# espertowatch_v2.net
KiCad netlist of a schematic drawn in EAGLE
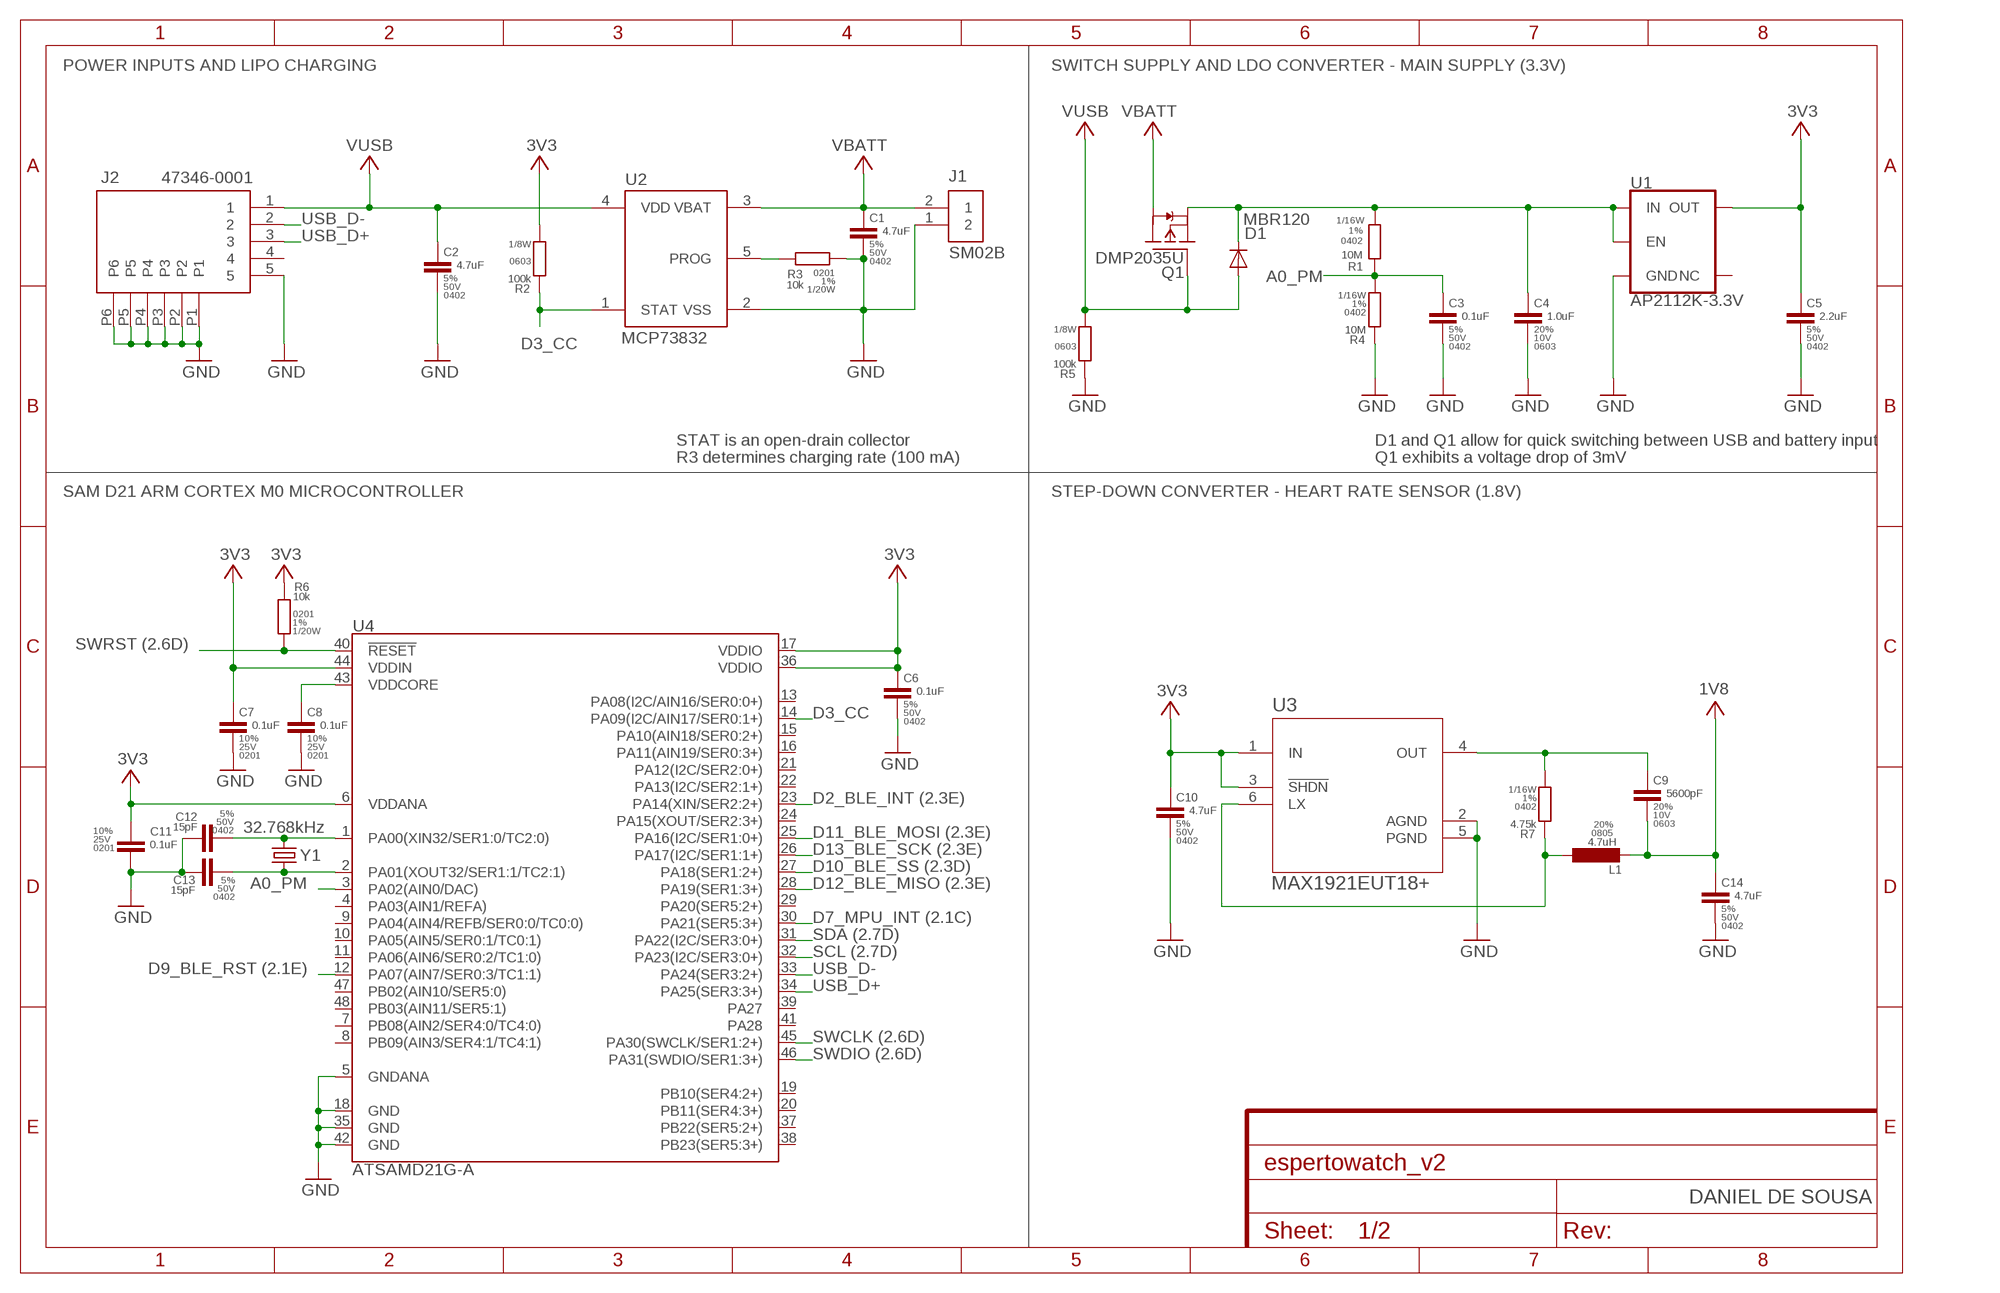
[diagram p0: schematic, sheet 1]
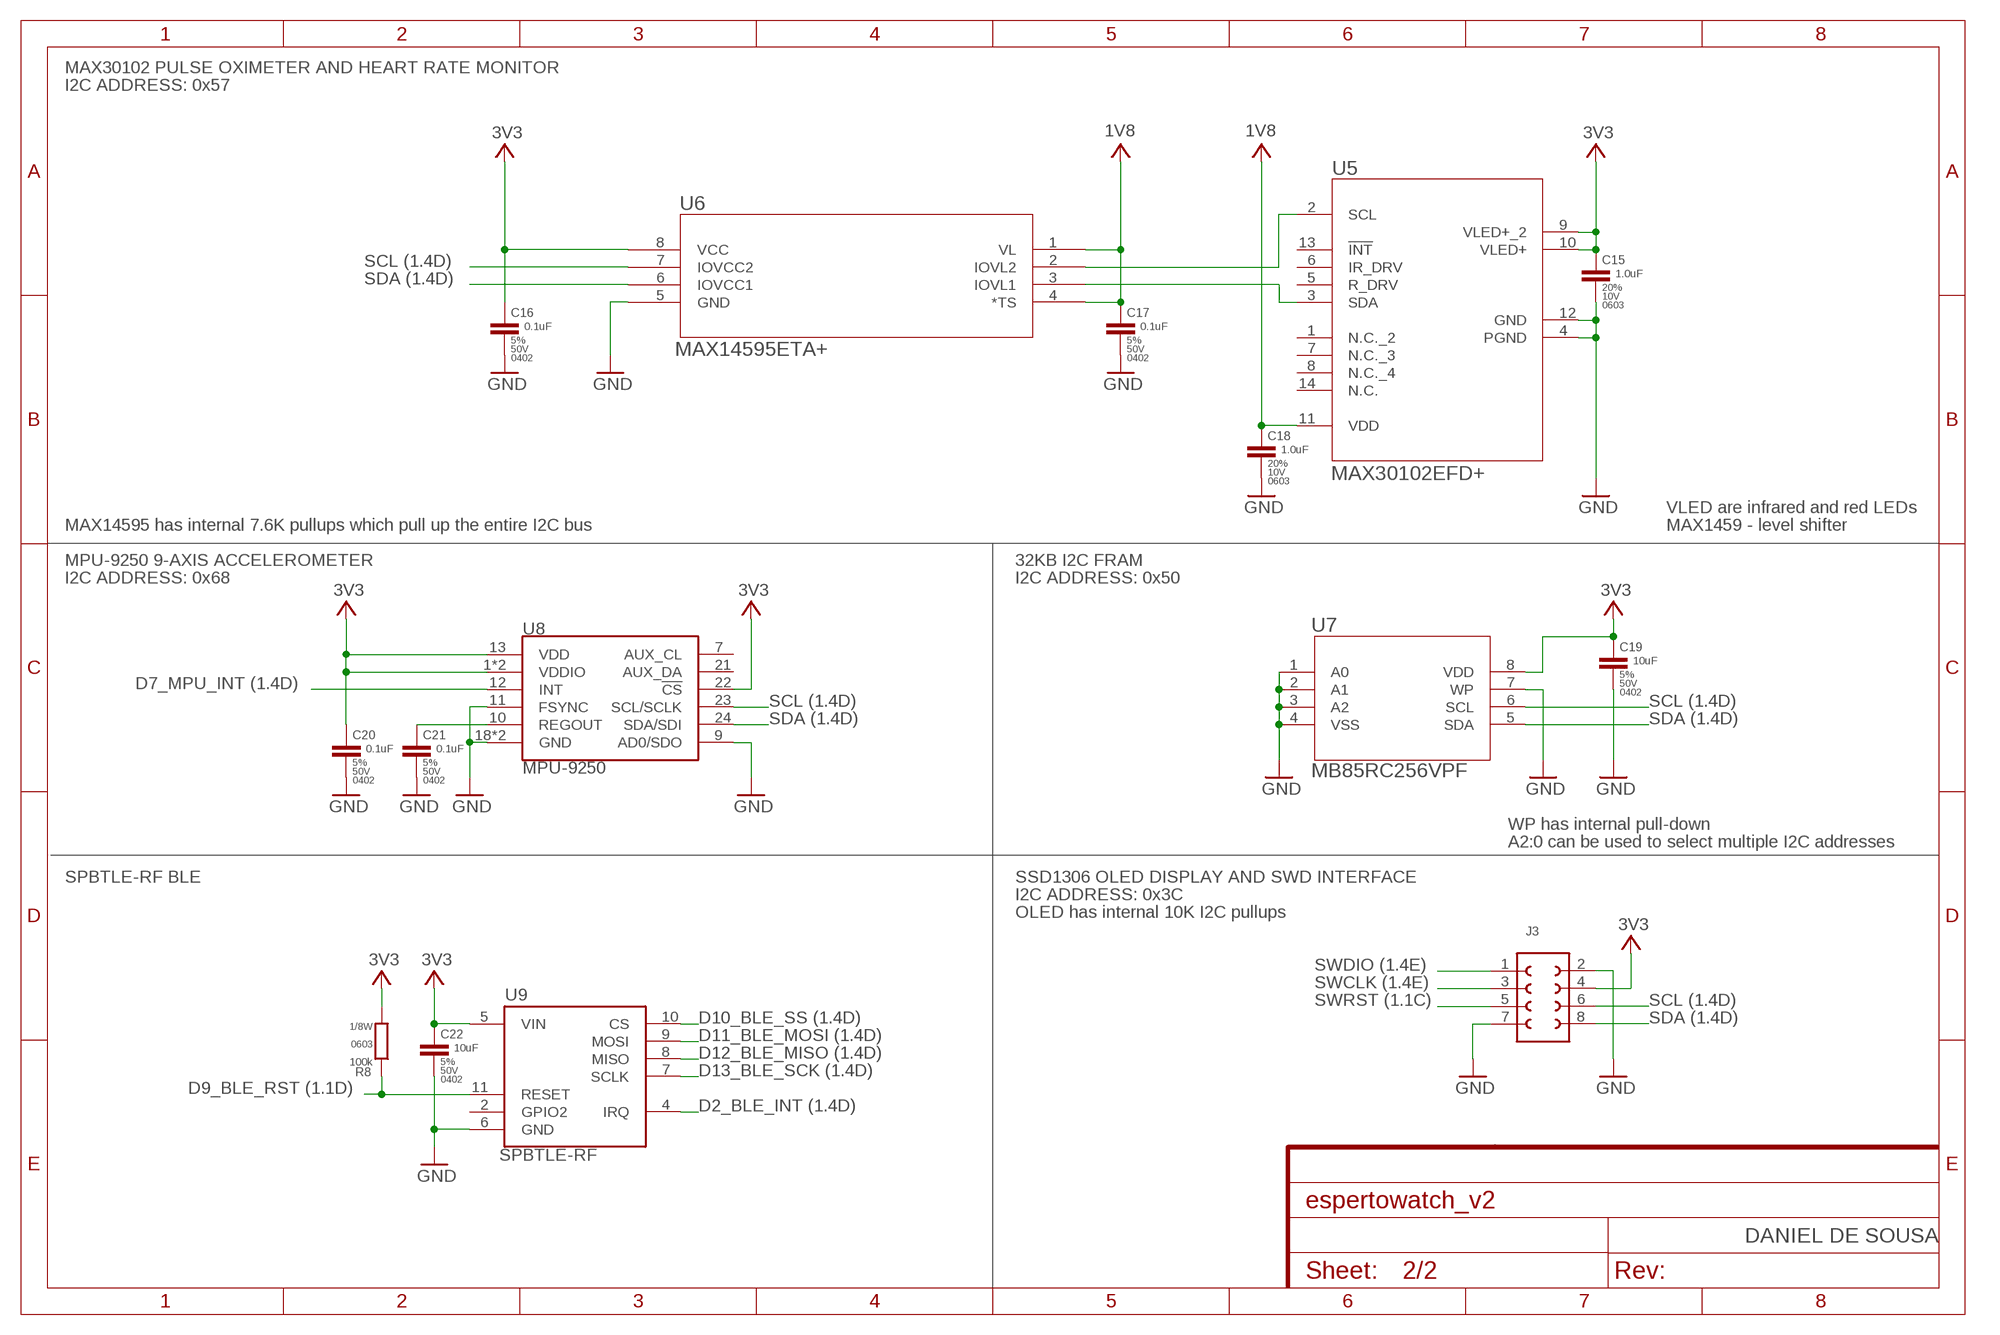
[diagram p1: schematic, sheet 2]

(export (version "E")
  (design (tool "Eeschema 10.0.6"))
  (components
    (comp (ref "C1")
      (value "4.7uF")
      (footprint "eagle-import:C0402_MURATA_GRM15-GJM15")
      (fields (field (name "TOLERANCE") "5%"))
      (libsource (lib "eagle-import") (part "C-EUC0402_MURATA_GRM15-GJM15"))
    )
    (comp (ref "C2")
      (value "4.7uF")
      (footprint "eagle-import:C0402_MURATA_GRM15-GJM15")
      (fields (field (name "TOLERANCE") "5%"))
      (libsource (lib "eagle-import") (part "C-EUC0402_MURATA_GRM15-GJM15"))
    )
    (comp (ref "C3")
      (value "0.1uF")
      (footprint "eagle-import:C0402_MURATA_GRM15-GJM15")
      (fields (field (name "TOLERANCE") "5%"))
      (libsource (lib "eagle-import") (part "C-EUC0402_MURATA_GRM15-GJM15"))
    )
    (comp (ref "C4")
      (value "1.0uF")
      (footprint "eagle-import:C0603_MURATA_GRM18")
      (fields (field (name "TOLERANCE") "20%"))
      (libsource (lib "eagle-import") (part "C-EUC0603_MURATA_GRM18"))
    )
    (comp (ref "C5")
      (value "2.2uF")
      (footprint "eagle-import:C0402_MURATA_GRM15-GJM15")
      (fields (field (name "TOLERANCE") "5%"))
      (libsource (lib "eagle-import") (part "C-EUC0402_MURATA_GRM15-GJM15"))
    )
    (comp (ref "C6")
      (value "0.1uF")
      (footprint "eagle-import:C0402_MURATA_GRM15-GJM15")
      (fields (field (name "TOLERANCE") "5%"))
      (libsource (lib "eagle-import") (part "C-EUC0402_MURATA_GRM15-GJM15"))
    )
    (comp (ref "C7")
      (value "0.1uF")
      (footprint "eagle-import:C0201_MURATA_GRM03")
      (fields (field (name "TOLERANCE") "10%"))
      (libsource (lib "eagle-import") (part "C-EUC0201_MURATA_GRM03"))
    )
    (comp (ref "C8")
      (value "0.1uF")
      (footprint "eagle-import:C0201_MURATA_GRM03")
      (fields (field (name "TOLERANCE") "10%"))
      (libsource (lib "eagle-import") (part "C-EUC0201_MURATA_GRM03"))
    )
    (comp (ref "C9")
      (value "5600pF")
      (footprint "eagle-import:C0603_MURATA_GRM18")
      (fields (field (name "TOLERANCE") "20%"))
      (libsource (lib "eagle-import") (part "C-EUC0603_MURATA_GRM18"))
    )
    (comp (ref "C10")
      (value "4.7uF")
      (footprint "eagle-import:C0402_MURATA_GRM15-GJM15")
      (fields (field (name "TOLERANCE") "5%"))
      (libsource (lib "eagle-import") (part "C-EUC0402_MURATA_GRM15-GJM15"))
    )
    (comp (ref "C11")
      (value "0.1uF")
      (footprint "eagle-import:C0201_MURATA_GRM03")
      (fields (field (name "RATING") "25V") (field (name "TOLERANCE") "10%") (field (name "PACKAGE") "0201"))
      (libsource (lib "eagle-import") (part "C-EUC0201_MURATA_GRM03"))
    )
    (comp (ref "C12")
      (value "15pF")
      (footprint "eagle-import:C0402_MURATA_GRM15-GJM15")
      (fields (field (name "RATING") "50V") (field (name "TOLERANCE") "5%") (field (name "PACKAGE") "0402"))
      (libsource (lib "eagle-import") (part "C-EUC0402_MURATA_GRM15-GJM15"))
    )
    (comp (ref "C13")
      (value "15pF")
      (footprint "eagle-import:C0402_MURATA_GRM15-GJM15")
      (fields (field (name "RATING") "50V") (field (name "TOLERANCE") "5%") (field (name "PACKAGE") "0402"))
      (libsource (lib "eagle-import") (part "C-EUC0402_MURATA_GRM15-GJM15"))
    )
    (comp (ref "C14")
      (value "4.7uF")
      (footprint "eagle-import:C0402_MURATA_GRM15-GJM15")
      (fields (field (name "TOLERANCE") "5%"))
      (libsource (lib "eagle-import") (part "C-EUC0402_MURATA_GRM15-GJM15"))
    )
    (comp (ref "D1")
      (value "MBR120")
      (footprint "eagle-import:SOD-123FL")
      (fields (field (name "PARTNO") "AS-ITM-00111"))
      (libsource (lib "eagle-import") (part "AS-ITM-00111"))
    )
    (comp (ref "J1")
      (value "SM02B")
      (footprint "eagle-import:JST_SH_2X1")
      (fields (field (name "PARTNO") "AS-ITM-00231"))
      (libsource (lib "eagle-import") (part "AS-ITM-00231"))
    )
    (comp (ref "J2")
      (value "47346-0001")
      (footprint "eagle-import:MICRO_USB")
      (fields (field (name "PARTNO") "AS-ITM-00021"))
      (libsource (lib "eagle-import") (part "AS-ITM-00021"))
    )
    (comp (ref "L1")
      (value "4.7uH")
      (footprint "eagle-import:L0805_TDK_MLZ")
      (fields (field (name "TOLERANCE") "20%"))
      (libsource (lib "eagle-import") (part "L-EUL0805_TDK_MLZ"))
    )
    (comp (ref "Q1")
      (value "DMP2035U")
      (footprint "eagle-import:SOT23")
      (fields (field (name "PARTNO") "AS-ITM-00024"))
      (libsource (lib "eagle-import") (part "AS-ITM-00024"))
    )
    (comp (ref "R1")
      (value "10M")
      (footprint "eagle-import:R0402_VISHAY_CRCW0402")
      (fields (field (name "TOLERANCE") "1%") (field (name "RATING") "1/16W") (field (name "PACKAGE") "0402"))
      (libsource (lib "eagle-import") (part "CRCW04021M00FKED"))
    )
    (comp (ref "R2")
      (value "100k")
      (footprint "eagle-import:R0603_VISHAY_MCT0603")
      (libsource (lib "eagle-import") (part "R-EU_R0603_VISHAY_MCT0603"))
    )
    (comp (ref "R3")
      (value "10k")
      (footprint "eagle-import:R0201_VISHAY_CRCW0201")
      (fields (field (name "TOLERANCE") "1%") (field (name "RATING") "1/20W") (field (name "PACKAGE") "0201"))
      (libsource (lib "eagle-import") (part "CRCW020110K0FKED"))
    )
    (comp (ref "R4")
      (value "10M")
      (footprint "eagle-import:R0402_VISHAY_CRCW0402")
      (fields (field (name "TOLERANCE") "1%"))
      (libsource (lib "eagle-import") (part "CRCW04021M00FKED"))
    )
    (comp (ref "R5")
      (value "100k")
      (footprint "eagle-import:R0603_VISHAY_MCT0603")
      (libsource (lib "eagle-import") (part "R-EU_R0603_VISHAY_MCT0603"))
    )
    (comp (ref "R6")
      (value "10k")
      (footprint "eagle-import:R0201_VISHAY_CRCW0201")
      (fields (field (name "TOLERANCE") "1%"))
      (libsource (lib "eagle-import") (part "CRCW020110K0FKED"))
    )
    (comp (ref "R7")
      (value "4.75k")
      (footprint "eagle-import:R0402_VISHAY_CRCW0402")
      (fields (field (name "TOLERANCE") "1%"))
      (libsource (lib "eagle-import") (part "R-EU_R0402_VISHAY_CRCW0402"))
    )
    (comp (ref "U1")
      (value "AP2112K-3.3V")
      (footprint "eagle-import:SOT23-5")
      (libsource (lib "eagle-import") (part "V_REG_AP2112K-3.3V"))
    )
    (comp (ref "U2")
      (value "MCP73832")
      (footprint "eagle-import:SOT-23")
      (fields (field (name "PARTNO") "AS-ITM-00136"))
      (libsource (lib "eagle-import") (part "AS-ITM-00136"))
    )
    (comp (ref "U3")
      (value "MAX1921EUT18+")
      (footprint "eagle-import:21-0058I")
      (fields (field (name "MANUFACTURER_PART_NUMBER") "MAX1921EUT18+T"))
      (libsource (lib "eagle-import") (part "MAX1921EUT18+T"))
    )
    (comp (ref "U4")
      (value "ATSAMD21G-A")
      (footprint "eagle-import:TQFP-48")
      (libsource (lib "eagle-import") (part "ATSAMD21G-A"))
    )
    (comp (ref "Y1")
      (value "32.768kHz")
      (footprint "eagle-import:CRYSTAL-SMD-3.2X1.5MM")
      (libsource (lib "eagle-import") (part "CRYSTAL-32.768KHZSMD-3.2X1.5"))
    )
    (comp (ref "C15")
      (value "1.0uF")
      (footprint "eagle-import:C0603_MURATA_GRM18")
      (fields (field (name "TOLERANCE") "20%"))
      (libsource (lib "eagle-import") (part "C-EUC0603_MURATA_GRM18"))
    )
    (comp (ref "C16")
      (value "0.1uF")
      (footprint "eagle-import:C0402_MURATA_GRM15-GJM15")
      (fields (field (name "TOLERANCE") "5%"))
      (libsource (lib "eagle-import") (part "C-EUC0402_MURATA_GRM15-GJM15"))
    )
    (comp (ref "C17")
      (value "0.1uF")
      (footprint "eagle-import:C0402_MURATA_GRM15-GJM15")
      (fields (field (name "TOLERANCE") "5%"))
      (libsource (lib "eagle-import") (part "C-EUC0402_MURATA_GRM15-GJM15"))
    )
    (comp (ref "C18")
      (value "1.0uF")
      (footprint "eagle-import:C0603_MURATA_GRM18")
      (fields (field (name "TOLERANCE") "20%"))
      (libsource (lib "eagle-import") (part "C-EUC0603_MURATA_GRM18"))
    )
    (comp (ref "C19")
      (value "10uF")
      (footprint "eagle-import:C0402_MURATA_GRM15-GJM15")
      (fields (field (name "TOLERANCE") "5%"))
      (libsource (lib "eagle-import") (part "C-EUC0402_MURATA_GRM15-GJM15"))
    )
    (comp (ref "C20")
      (value "0.1uF")
      (footprint "eagle-import:C0402_MURATA_GRM15-GJM15")
      (fields (field (name "TOLERANCE") "5%"))
      (libsource (lib "eagle-import") (part "C-EUC0402_MURATA_GRM15-GJM15"))
    )
    (comp (ref "C21")
      (value "0.1uF")
      (footprint "eagle-import:C0402_MURATA_GRM15-GJM15")
      (fields (field (name "TOLERANCE") "5%"))
      (libsource (lib "eagle-import") (part "C-EUC0402_MURATA_GRM15-GJM15"))
    )
    (comp (ref "C22")
      (value "10uF")
      (footprint "eagle-import:C0402_MURATA_GRM15-GJM15")
      (fields (field (name "TOLERANCE") "5%"))
      (libsource (lib "eagle-import") (part "C-EUC0402_MURATA_GRM15-GJM15"))
    )
    (comp (ref "J3")
      (value "610X08243021")
      (footprint "eagle-import:610X08243021")
      (libsource (lib "eagle-import") (part "610X08243021"))
    )
    (comp (ref "R8")
      (value "100k")
      (footprint "eagle-import:R0603_VISHAY_MCT0603")
      (libsource (lib "eagle-import") (part "R-EU_R0603_VISHAY_MCT0603"))
    )
    (comp (ref "U5")
      (value "MAX30102EFD+")
      (footprint "eagle-import:21-0880B-M")
      (libsource (lib "eagle-import") (part "MAX30102EFD+21-0880B-M"))
    )
    (comp (ref "U6")
      (value "MAX14595ETA+")
      (footprint "eagle-import:21-0487A")
      (fields
        (field (name "DIGI-KEY_PART_NUMBER") "MAX14595ETA+TCT-ND")
        (field (name "MF") "Maxim Integrated")
        (field (name "MP") "MAX14595ETA+T")
      )
      (libsource (lib "eagle-import") (part "MAX14595ETAT"))
    )
    (comp (ref "U7")
      (value "MB85RC256VPF")
      (footprint "eagle-import:FPT-8P-M02")
      (fields (field (name "MANUFACTURER_PART_NUMBER") "Inc."))
      (libsource (lib "eagle-import") (part "INC."))
    )
    (comp (ref "U8")
      (value "MPU-9250")
      (footprint "eagle-import:QFN24-3X3")
      (libsource (lib "eagle-import") (part "MPU-9250"))
    )
    (comp (ref "U9")
      (value "SPBTLE-RF")
      (footprint "eagle-import:SPBTLE-RF")
      (fields (field (name "PARTNO") "AS-ITM-00294"))
      (libsource (lib "eagle-import") (part "AS-ITM-00294"))
    )
  )
  (nets
    (net (code "1") (name "1V8") (class "Default")
      (node (ref "C14") (pin "1") (pinfunction "1_1") (pintype "passive"))
      (node (ref "C17") (pin "1") (pinfunction "1_1") (pintype "passive"))
      (node (ref "C18") (pin "1") (pinfunction "1_1") (pintype "passive"))
      (node (ref "C9") (pin "2") (pinfunction "2_2") (pintype "passive"))
      (node (ref "L1") (pin "P$2") (pinfunction "2_P$2") (pintype "passive"))
      (node (ref "U5") (pin "11") (pinfunction "VDD_11") (pintype "power_in"))
      (node (ref "U6") (pin "1") (pinfunction "VL_1") (pintype "power_in"))
      (node (ref "U6") (pin "4") (pinfunction "*TS_4") (pintype "passive"))
    )
    (net (code "2") (name "3V3") (class "Default")
      (node (ref "C10") (pin "1") (pinfunction "1_1") (pintype "passive"))
      (node (ref "C11") (pin "1") (pinfunction "1_1") (pintype "passive"))
      (node (ref "C15") (pin "1") (pinfunction "1_1") (pintype "passive"))
      (node (ref "C16") (pin "1") (pinfunction "1_1") (pintype "passive"))
      (node (ref "C19") (pin "1") (pinfunction "1_1") (pintype "passive"))
      (node (ref "C20") (pin "1") (pinfunction "1_1") (pintype "passive"))
      (node (ref "C22") (pin "1") (pinfunction "1_1") (pintype "passive"))
      (node (ref "C5") (pin "1") (pinfunction "1_1") (pintype "passive"))
      (node (ref "C6") (pin "1") (pinfunction "1_1") (pintype "passive"))
      (node (ref "C7") (pin "1") (pinfunction "1_1") (pintype "passive"))
      (node (ref "J3") (pin "4") (pinfunction "7_4") (pintype "passive"))
      (node (ref "R2") (pin "2") (pinfunction "2_2") (pintype "passive"))
      (node (ref "R6") (pin "1") (pinfunction "1_1") (pintype "passive"))
      (node (ref "R8") (pin "2") (pinfunction "2_2") (pintype "passive"))
      (node (ref "U1") (pin "5") (pinfunction "OUT_5") (pintype "passive"))
      (node (ref "U3") (pin "1") (pinfunction "IN_1") (pintype "input"))
      (node (ref "U3") (pin "3") (pinfunction "~{SHDN}_3") (pintype "passive"))
      (node (ref "U4") (pin "17") (pinfunction "VDDIO_17") (pintype "bidirectional"))
      (node (ref "U4") (pin "36") (pinfunction "VDDIO_36") (pintype "bidirectional"))
      (node (ref "U4") (pin "44") (pinfunction "VDDIN_44") (pintype "bidirectional"))
      (node (ref "U4") (pin "6") (pinfunction "VDDANA_6") (pintype "bidirectional"))
      (node (ref "U5") (pin "10") (pinfunction "VLED+_10") (pintype "passive"))
      (node (ref "U5") (pin "9") (pinfunction "VLED+_2_9") (pintype "passive"))
      (node (ref "U6") (pin "8") (pinfunction "VCC_8") (pintype "power_in"))
      (node (ref "U7") (pin "8") (pinfunction "VDD_8") (pintype "power_in"))
      (node (ref "U8") (pin "1") (pinfunction "VDDIO_1") (pintype "bidirectional"))
      (node (ref "U8") (pin "13") (pinfunction "VDD_13") (pintype "bidirectional"))
      (node (ref "U8") (pin "22") (pinfunction "~{CS}_22") (pintype "bidirectional"))
      (node (ref "U8") (pin "8") (pinfunction "VDDIO_8") (pintype "bidirectional"))
      (node (ref "U9") (pin "5") (pinfunction "VIN_5") (pintype "bidirectional"))
    )
    (net (code "3") (name "A0_PM") (class "Default")
      (node (ref "C3") (pin "1") (pinfunction "1_1") (pintype "passive"))
      (node (ref "R1") (pin "1") (pinfunction "1_1") (pintype "passive"))
      (node (ref "R4") (pin "2") (pinfunction "2_2") (pintype "passive"))
      (node (ref "U4") (pin "3") (pinfunction "PA02(AIN0/DAC)_3") (pintype "bidirectional"))
    )
    (net (code "4") (name "D2_BLE_INT") (class "Default")
      (node (ref "U4") (pin "23") (pinfunction "PA14(XIN/SER2:2+)_23") (pintype "bidirectional"))
      (node (ref "U9") (pin "4") (pinfunction "IRQ_4") (pintype "bidirectional"))
    )
    (net (code "5") (name "D3_CC") (class "Default")
      (node (ref "R2") (pin "1") (pinfunction "1_1") (pintype "passive"))
      (node (ref "U2") (pin "1") (pinfunction "STAT_1") (pintype "bidirectional"))
      (node (ref "U4") (pin "14") (pinfunction "PA09(I2C/AIN17/SER0:1+)_14") (pintype "bidirectional"))
    )
    (net (code "6") (name "D7_MPU_INT") (class "Default")
      (node (ref "U4") (pin "30") (pinfunction "PA21(SER5:3+)_30") (pintype "bidirectional"))
      (node (ref "U8") (pin "12") (pinfunction "INT_12") (pintype "bidirectional"))
    )
    (net (code "7") (name "D9_BLE_RST") (class "Default")
      (node (ref "R8") (pin "1") (pinfunction "1_1") (pintype "passive"))
      (node (ref "U4") (pin "12") (pinfunction "PA07(AIN7/SER0:3/TC1:1)_12") (pintype "bidirectional"))
      (node (ref "U9") (pin "11") (pinfunction "RESET_11") (pintype "bidirectional"))
    )
    (net (code "8") (name "D10_BLE_SS") (class "Default")
      (node (ref "U4") (pin "27") (pinfunction "PA18(SER1:2+)_27") (pintype "bidirectional"))
      (node (ref "U9") (pin "10") (pinfunction "CS_10") (pintype "bidirectional"))
    )
    (net (code "9") (name "D11_BLE_MOSI") (class "Default")
      (node (ref "U4") (pin "25") (pinfunction "PA16(I2C/SER1:0+)_25") (pintype "bidirectional"))
      (node (ref "U9") (pin "9") (pinfunction "MOSI_9") (pintype "bidirectional"))
    )
    (net (code "10") (name "D12_BLE_MISO") (class "Default")
      (node (ref "U4") (pin "28") (pinfunction "PA19(SER1:3+)_28") (pintype "bidirectional"))
      (node (ref "U9") (pin "8") (pinfunction "MISO_8") (pintype "bidirectional"))
    )
    (net (code "11") (name "D13_BLE_SCK") (class "Default")
      (node (ref "U4") (pin "26") (pinfunction "PA17(I2C/SER1:1+)_26") (pintype "bidirectional"))
      (node (ref "U9") (pin "7") (pinfunction "SCLK_7") (pintype "bidirectional"))
    )
    (net (code "12") (name "GND") (class "Default")
      (node (ref "C1") (pin "2") (pinfunction "2_2") (pintype "passive"))
      (node (ref "C10") (pin "2") (pinfunction "2_2") (pintype "passive"))
      (node (ref "C11") (pin "2") (pinfunction "2_2") (pintype "passive"))
      (node (ref "C12") (pin "1") (pinfunction "1_1") (pintype "passive"))
      (node (ref "C13") (pin "1") (pinfunction "1_1") (pintype "passive"))
      (node (ref "C14") (pin "2") (pinfunction "2_2") (pintype "passive"))
      (node (ref "C15") (pin "2") (pinfunction "2_2") (pintype "passive"))
      (node (ref "C16") (pin "2") (pinfunction "2_2") (pintype "passive"))
      (node (ref "C17") (pin "2") (pinfunction "2_2") (pintype "passive"))
      (node (ref "C18") (pin "2") (pinfunction "2_2") (pintype "passive"))
      (node (ref "C19") (pin "2") (pinfunction "2_2") (pintype "passive"))
      (node (ref "C2") (pin "2") (pinfunction "2_2") (pintype "passive"))
      (node (ref "C20") (pin "2") (pinfunction "2_2") (pintype "passive"))
      (node (ref "C21") (pin "2") (pinfunction "2_2") (pintype "passive"))
      (node (ref "C22") (pin "2") (pinfunction "2_2") (pintype "passive"))
      (node (ref "C3") (pin "2") (pinfunction "2_2") (pintype "passive"))
      (node (ref "C4") (pin "2") (pinfunction "2_2") (pintype "passive"))
      (node (ref "C5") (pin "2") (pinfunction "2_2") (pintype "passive"))
      (node (ref "C6") (pin "2") (pinfunction "2_2") (pintype "passive"))
      (node (ref "C7") (pin "2") (pinfunction "2_2") (pintype "passive"))
      (node (ref "C8") (pin "2") (pinfunction "2_2") (pintype "passive"))
      (node (ref "J1") (pin "1") (pinfunction "2_1") (pintype "bidirectional"))
      (node (ref "J2") (pin "5") (pinfunction "5_5") (pintype "bidirectional"))
      (node (ref "J2") (pin "P1") (pinfunction "P1_P1") (pintype "bidirectional"))
      (node (ref "J2") (pin "P2") (pinfunction "P2_P2") (pintype "bidirectional"))
      (node (ref "J2") (pin "P3") (pinfunction "P3_P3") (pintype "bidirectional"))
      (node (ref "J2") (pin "P4") (pinfunction "P4_P4") (pintype "bidirectional"))
      (node (ref "J2") (pin "P5") (pinfunction "P5_P5") (pintype "bidirectional"))
      (node (ref "J2") (pin "P6") (pinfunction "P6_P6") (pintype "bidirectional"))
      (node (ref "J3") (pin "2") (pinfunction "8_2") (pintype "passive"))
      (node (ref "J3") (pin "7") (pinfunction "4_7") (pintype "passive"))
      (node (ref "R3") (pin "2") (pinfunction "2_2") (pintype "passive"))
      (node (ref "R4") (pin "1") (pinfunction "1_1") (pintype "passive"))
      (node (ref "R5") (pin "1") (pinfunction "1_1") (pintype "passive"))
      (node (ref "U1") (pin "2") (pinfunction "GND_2") (pintype "input"))
      (node (ref "U2") (pin "2") (pinfunction "VSS_2") (pintype "bidirectional"))
      (node (ref "U3") (pin "2") (pinfunction "AGND_2") (pintype "power_in"))
      (node (ref "U3") (pin "5") (pinfunction "PGND_5") (pintype "power_in"))
      (node (ref "U4") (pin "18") (pinfunction "GND_18") (pintype "bidirectional"))
      (node (ref "U4") (pin "35") (pinfunction "GND_35") (pintype "bidirectional"))
      (node (ref "U4") (pin "42") (pinfunction "GND_42") (pintype "bidirectional"))
      (node (ref "U4") (pin "5") (pinfunction "GNDANA_5") (pintype "bidirectional"))
      (node (ref "U5") (pin "12") (pinfunction "GND_12") (pintype "power_in"))
      (node (ref "U5") (pin "4") (pinfunction "PGND_4") (pintype "power_in"))
      (node (ref "U6") (pin "5") (pinfunction "GND_5") (pintype "power_in"))
      (node (ref "U7") (pin "1") (pinfunction "A0_1") (pintype "input"))
      (node (ref "U7") (pin "2") (pinfunction "A1_2") (pintype "input"))
      (node (ref "U7") (pin "3") (pinfunction "A2_3") (pintype "input"))
      (node (ref "U7") (pin "4") (pinfunction "VSS_4") (pintype "power_in"))
      (node (ref "U7") (pin "7") (pinfunction "WP_7") (pintype "passive"))
      (node (ref "U8") (pin "11") (pinfunction "FSYNC_11") (pintype "bidirectional"))
      (node (ref "U8") (pin "18") (pinfunction "GND_18") (pintype "bidirectional"))
      (node (ref "U8") (pin "20") (pinfunction "GND_20") (pintype "bidirectional"))
      (node (ref "U8") (pin "9") (pinfunction "AD0/SDO_9") (pintype "bidirectional"))
      (node (ref "U9") (pin "6") (pinfunction "GND_6") (pintype "bidirectional"))
    )
    (net (code "13") (name "Net-(L1-1)") (class "Default")
      (node (ref "L1") (pin "P$1") (pinfunction "1_P$1") (pintype "passive"))
      (node (ref "R7") (pin "1") (pinfunction "1_1") (pintype "passive"))
      (node (ref "U3") (pin "6") (pinfunction "LX_6") (pintype "passive"))
    )
    (net (code "14") (name "Net-(Q1-S)") (class "Default")
      (node (ref "C4") (pin "1") (pinfunction "1_1") (pintype "passive"))
      (node (ref "D1") (pin "C") (pinfunction "C_C") (pintype "passive"))
      (node (ref "Q1") (pin "E") (pinfunction "S_E") (pintype "passive"))
      (node (ref "R1") (pin "2") (pinfunction "2_2") (pintype "passive"))
      (node (ref "U1") (pin "1") (pinfunction "IN_1") (pintype "input"))
      (node (ref "U1") (pin "3") (pinfunction "EN_3") (pintype "input"))
    )
    (net (code "15") (name "Net-(U2-PROG)") (class "Default")
      (node (ref "R3") (pin "1") (pinfunction "1_1") (pintype "passive"))
      (node (ref "U2") (pin "5") (pinfunction "PROG_5") (pintype "bidirectional"))
    )
    (net (code "16") (name "Net-(U3-OUT)") (class "Default")
      (node (ref "C9") (pin "1") (pinfunction "1_1") (pintype "passive"))
      (node (ref "R7") (pin "2") (pinfunction "2_2") (pintype "passive"))
      (node (ref "U3") (pin "4") (pinfunction "OUT_4") (pintype "output"))
    )
    (net (code "17") (name "Net-(U4-PA00(XIN32{slash}SER1:0{slash}TC2:0))") (class "Default")
      (node (ref "C12") (pin "2") (pinfunction "2_2") (pintype "passive"))
      (node (ref "U4") (pin "1") (pinfunction "PA00(XIN32/SER1:0/TC2:0)_1") (pintype "bidirectional"))
      (node (ref "Y1") (pin "P$2") (pinfunction "2_P$2") (pintype "passive"))
    )
    (net (code "18") (name "Net-(U4-PA01(XOUT32{slash}SER1:1{slash}TC2:1))") (class "Default")
      (node (ref "C13") (pin "2") (pinfunction "2_2") (pintype "passive"))
      (node (ref "U4") (pin "2") (pinfunction "PA01(XOUT32/SER1:1/TC2:1)_2") (pintype "bidirectional"))
      (node (ref "Y1") (pin "P$1") (pinfunction "1_P$1") (pintype "passive"))
    )
    (net (code "19") (name "Net-(U4-VDDCORE)") (class "Default")
      (node (ref "C8") (pin "1") (pinfunction "1_1") (pintype "passive"))
      (node (ref "U4") (pin "43") (pinfunction "VDDCORE_43") (pintype "bidirectional"))
    )
    (net (code "20") (name "Net-(U5-SCL)") (class "Default")
      (node (ref "U5") (pin "2") (pinfunction "SCL_2") (pintype "input"))
      (node (ref "U6") (pin "2") (pinfunction "IOVL2_2") (pintype "passive"))
    )
    (net (code "21") (name "Net-(U5-SDA)") (class "Default")
      (node (ref "U5") (pin "3") (pinfunction "SDA_3") (pintype "bidirectional"))
      (node (ref "U6") (pin "3") (pinfunction "IOVL1_3") (pintype "passive"))
    )
    (net (code "22") (name "Net-(U8-REGOUT)") (class "Default")
      (node (ref "C21") (pin "1") (pinfunction "1_1") (pintype "passive"))
      (node (ref "U8") (pin "10") (pinfunction "REGOUT_10") (pintype "bidirectional"))
    )
    (net (code "23") (name "SCL") (class "Default")
      (node (ref "J3") (pin "6") (pinfunction "6_6") (pintype "passive"))
      (node (ref "U4") (pin "32") (pinfunction "PA23(I2C/SER3:0+)_32") (pintype "bidirectional"))
      (node (ref "U6") (pin "7") (pinfunction "IOVCC2_7") (pintype "passive"))
      (node (ref "U7") (pin "6") (pinfunction "SCL_6") (pintype "input"))
      (node (ref "U8") (pin "23") (pinfunction "SCL/SCLK_23") (pintype "bidirectional"))
    )
    (net (code "24") (name "SDA") (class "Default")
      (node (ref "J3") (pin "8") (pinfunction "5_8") (pintype "passive"))
      (node (ref "U4") (pin "31") (pinfunction "PA22(I2C/SER3:0+)_31") (pintype "bidirectional"))
      (node (ref "U6") (pin "6") (pinfunction "IOVCC1_6") (pintype "passive"))
      (node (ref "U7") (pin "5") (pinfunction "SDA_5") (pintype "passive"))
      (node (ref "U8") (pin "24") (pinfunction "SDA/SDI_24") (pintype "bidirectional"))
    )
    (net (code "25") (name "SWCLK") (class "Default")
      (node (ref "J3") (pin "3") (pinfunction "2_3") (pintype "passive"))
      (node (ref "U4") (pin "45") (pinfunction "PA30(SWCLK/SER1:2+)_45") (pintype "bidirectional"))
    )
    (net (code "26") (name "SWDIO") (class "Default")
      (node (ref "J3") (pin "1") (pinfunction "1_1") (pintype "passive"))
      (node (ref "U4") (pin "46") (pinfunction "PA31(SWDIO/SER1:3+)_46") (pintype "bidirectional"))
    )
    (net (code "27") (name "SWRST") (class "Default")
      (node (ref "J3") (pin "5") (pinfunction "3_5") (pintype "passive"))
      (node (ref "R6") (pin "2") (pinfunction "2_2") (pintype "passive"))
      (node (ref "U4") (pin "40") (pinfunction "~{RESET}_40") (pintype "bidirectional"))
    )
    (net (code "28") (name "USB_D+") (class "Default")
      (node (ref "J2") (pin "3") (pinfunction "3_3") (pintype "bidirectional"))
      (node (ref "U4") (pin "34") (pinfunction "PA25(SER3:3+)_34") (pintype "bidirectional"))
    )
    (net (code "29") (name "USB_D-") (class "Default")
      (node (ref "J2") (pin "2") (pinfunction "2_2") (pintype "bidirectional"))
      (node (ref "U4") (pin "33") (pinfunction "PA24(SER3:2+)_33") (pintype "bidirectional"))
    )
    (net (code "30") (name "VBATT") (class "Default")
      (node (ref "C1") (pin "1") (pinfunction "1_1") (pintype "passive"))
      (node (ref "J1") (pin "2") (pinfunction "1_2") (pintype "bidirectional"))
      (node (ref "Q1") (pin "C") (pinfunction "D_C") (pintype "passive"))
      (node (ref "U2") (pin "3") (pinfunction "VBAT_3") (pintype "bidirectional"))
    )
    (net (code "31") (name "VUSB") (class "Default")
      (node (ref "C2") (pin "1") (pinfunction "1_1") (pintype "passive"))
      (node (ref "D1") (pin "A") (pinfunction "A_A") (pintype "passive"))
      (node (ref "J2") (pin "1") (pinfunction "1_1") (pintype "bidirectional"))
      (node (ref "Q1") (pin "B") (pinfunction "G_B") (pintype "passive"))
      (node (ref "R5") (pin "2") (pinfunction "2_2") (pintype "passive"))
      (node (ref "U2") (pin "4") (pinfunction "VDD_4") (pintype "bidirectional"))
    )
    (net (code "32") (name "unconnected-(J2-Pad4)") (class "Default")
      (node (ref "J2") (pin "4") (pinfunction "4_4") (pintype "bidirectional"))
    )
    (net (code "33") (name "unconnected-(U1-NC-Pad4)") (class "Default")
      (node (ref "U1") (pin "4") (pinfunction "NC_4") (pintype "no_connect"))
    )
    (net (code "34") (name "unconnected-(U4-PA03(AIN1{slash}REFA)-Pad4)") (class "Default")
      (node (ref "U4") (pin "4") (pinfunction "PA03(AIN1/REFA)_4") (pintype "bidirectional"))
    )
    (net (code "35") (name "unconnected-(U4-PA04(AIN4{slash}REFB{slash}SER0:0{slash}TC0:0)-Pad9)") (class "Default")
      (node (ref "U4") (pin "9") (pinfunction "PA04(AIN4/REFB/SER0:0/TC0:0)_9") (pintype "bidirectional"))
    )
    (net (code "36") (name "unconnected-(U4-PA05(AIN5{slash}SER0:1{slash}TC0:1)-Pad10)") (class "Default")
      (node (ref "U4") (pin "10") (pinfunction "PA05(AIN5/SER0:1/TC0:1)_10") (pintype "bidirectional"))
    )
    (net (code "37") (name "unconnected-(U4-PA06(AIN6{slash}SER0:2{slash}TC1:0)-Pad11)") (class "Default")
      (node (ref "U4") (pin "11") (pinfunction "PA06(AIN6/SER0:2/TC1:0)_11") (pintype "bidirectional"))
    )
    (net (code "38") (name "unconnected-(U4-PA08(I2C{slash}AIN16{slash}SER0:0+)-Pad13)") (class "Default")
      (node (ref "U4") (pin "13") (pinfunction "PA08(I2C/AIN16/SER0:0+)_13") (pintype "bidirectional"))
    )
    (net (code "39") (name "unconnected-(U4-PA10(AIN18{slash}SER0:2+)-Pad15)") (class "Default")
      (node (ref "U4") (pin "15") (pinfunction "PA10(AIN18/SER0:2+)_15") (pintype "bidirectional"))
    )
    (net (code "40") (name "unconnected-(U4-PA11(AIN19{slash}SER0:3+)-Pad16)") (class "Default")
      (node (ref "U4") (pin "16") (pinfunction "PA11(AIN19/SER0:3+)_16") (pintype "bidirectional"))
    )
    (net (code "41") (name "unconnected-(U4-PA12(I2C{slash}SER2:0+)-Pad21)") (class "Default")
      (node (ref "U4") (pin "21") (pinfunction "PA12(I2C/SER2:0+)_21") (pintype "bidirectional"))
    )
    (net (code "42") (name "unconnected-(U4-PA13(I2C{slash}SER2:1+)-Pad22)") (class "Default")
      (node (ref "U4") (pin "22") (pinfunction "PA13(I2C/SER2:1+)_22") (pintype "bidirectional"))
    )
    (net (code "43") (name "unconnected-(U4-PA15(XOUT{slash}SER2:3+)-Pad24)") (class "Default")
      (node (ref "U4") (pin "24") (pinfunction "PA15(XOUT/SER2:3+)_24") (pintype "bidirectional"))
    )
    (net (code "44") (name "unconnected-(U4-PA20(SER5:2+)-Pad29)") (class "Default")
      (node (ref "U4") (pin "29") (pinfunction "PA20(SER5:2+)_29") (pintype "bidirectional"))
    )
    (net (code "45") (name "unconnected-(U4-PA27-Pad39)") (class "Default")
      (node (ref "U4") (pin "39") (pinfunction "PA27_39") (pintype "bidirectional"))
    )
    (net (code "46") (name "unconnected-(U4-PA28-Pad41)") (class "Default")
      (node (ref "U4") (pin "41") (pinfunction "PA28_41") (pintype "bidirectional"))
    )
    (net (code "47") (name "unconnected-(U4-PB02(AIN10{slash}SER5:0)-Pad47)") (class "Default")
      (node (ref "U4") (pin "47") (pinfunction "PB02(AIN10/SER5:0)_47") (pintype "bidirectional"))
    )
    (net (code "48") (name "unconnected-(U4-PB03(AIN11{slash}SER5:1)-Pad48)") (class "Default")
      (node (ref "U4") (pin "48") (pinfunction "PB03(AIN11/SER5:1)_48") (pintype "bidirectional"))
    )
    (net (code "49") (name "unconnected-(U4-PB08(AIN2{slash}SER4:0{slash}TC4:0)-Pad7)") (class "Default")
      (node (ref "U4") (pin "7") (pinfunction "PB08(AIN2/SER4:0/TC4:0)_7") (pintype "bidirectional"))
    )
    (net (code "50") (name "unconnected-(U4-PB09(AIN3{slash}SER4:1{slash}TC4:1)-Pad8)") (class "Default")
      (node (ref "U4") (pin "8") (pinfunction "PB09(AIN3/SER4:1/TC4:1)_8") (pintype "bidirectional"))
    )
    (net (code "51") (name "unconnected-(U4-PB10(SER4:2+)-Pad19)") (class "Default")
      (node (ref "U4") (pin "19") (pinfunction "PB10(SER4:2+)_19") (pintype "bidirectional"))
    )
    (net (code "52") (name "unconnected-(U4-PB11(SER4:3+)-Pad20)") (class "Default")
      (node (ref "U4") (pin "20") (pinfunction "PB11(SER4:3+)_20") (pintype "bidirectional"))
    )
    (net (code "53") (name "unconnected-(U4-PB22(SER5:2+)-Pad37)") (class "Default")
      (node (ref "U4") (pin "37") (pinfunction "PB22(SER5:2+)_37") (pintype "bidirectional"))
    )
    (net (code "54") (name "unconnected-(U4-PB23(SER5:3+)-Pad38)") (class "Default")
      (node (ref "U4") (pin "38") (pinfunction "PB23(SER5:3+)_38") (pintype "bidirectional"))
    )
    (net (code "55") (name "unconnected-(U5-IR_DRV-Pad6)") (class "Default")
      (node (ref "U5") (pin "6") (pinfunction "IR_DRV_6") (pintype "passive"))
    )
    (net (code "56") (name "unconnected-(U5-N.C.-Pad14)") (class "Default")
      (node (ref "U5") (pin "14") (pinfunction "N.C._14") (pintype "no_connect"))
    )
    (net (code "57") (name "unconnected-(U5-N.C._2-Pad1)") (class "Default")
      (node (ref "U5") (pin "1") (pinfunction "N.C._2_1") (pintype "no_connect"))
    )
    (net (code "58") (name "unconnected-(U5-N.C._3-Pad7)") (class "Default")
      (node (ref "U5") (pin "7") (pinfunction "N.C._3_7") (pintype "no_connect"))
    )
    (net (code "59") (name "unconnected-(U5-N.C._4-Pad8)") (class "Default")
      (node (ref "U5") (pin "8") (pinfunction "N.C._4_8") (pintype "no_connect"))
    )
    (net (code "60") (name "unconnected-(U5-R_DRV-Pad5)") (class "Default")
      (node (ref "U5") (pin "5") (pinfunction "R_DRV_5") (pintype "passive"))
    )
    (net (code "61") (name "unconnected-(U5-~{INT}-Pad13)") (class "Default")
      (node (ref "U5") (pin "13") (pinfunction "~{INT}_13") (pintype "passive"))
    )
    (net (code "62") (name "unconnected-(U8-AUX_CL-Pad7)") (class "Default")
      (node (ref "U8") (pin "7") (pinfunction "AUX_CL_7") (pintype "bidirectional"))
    )
    (net (code "63") (name "unconnected-(U8-AUX_DA-Pad21)") (class "Default")
      (node (ref "U8") (pin "21") (pinfunction "AUX_DA_21") (pintype "bidirectional"))
    )
    (net (code "64") (name "unconnected-(U9-GPIO2-Pad2)") (class "Default")
      (node (ref "U9") (pin "2") (pinfunction "GPIO2_2") (pintype "bidirectional"))
    )
  )
)
